# jmb575.net
KiCad netlist of a schematic drawn in Altium Designer
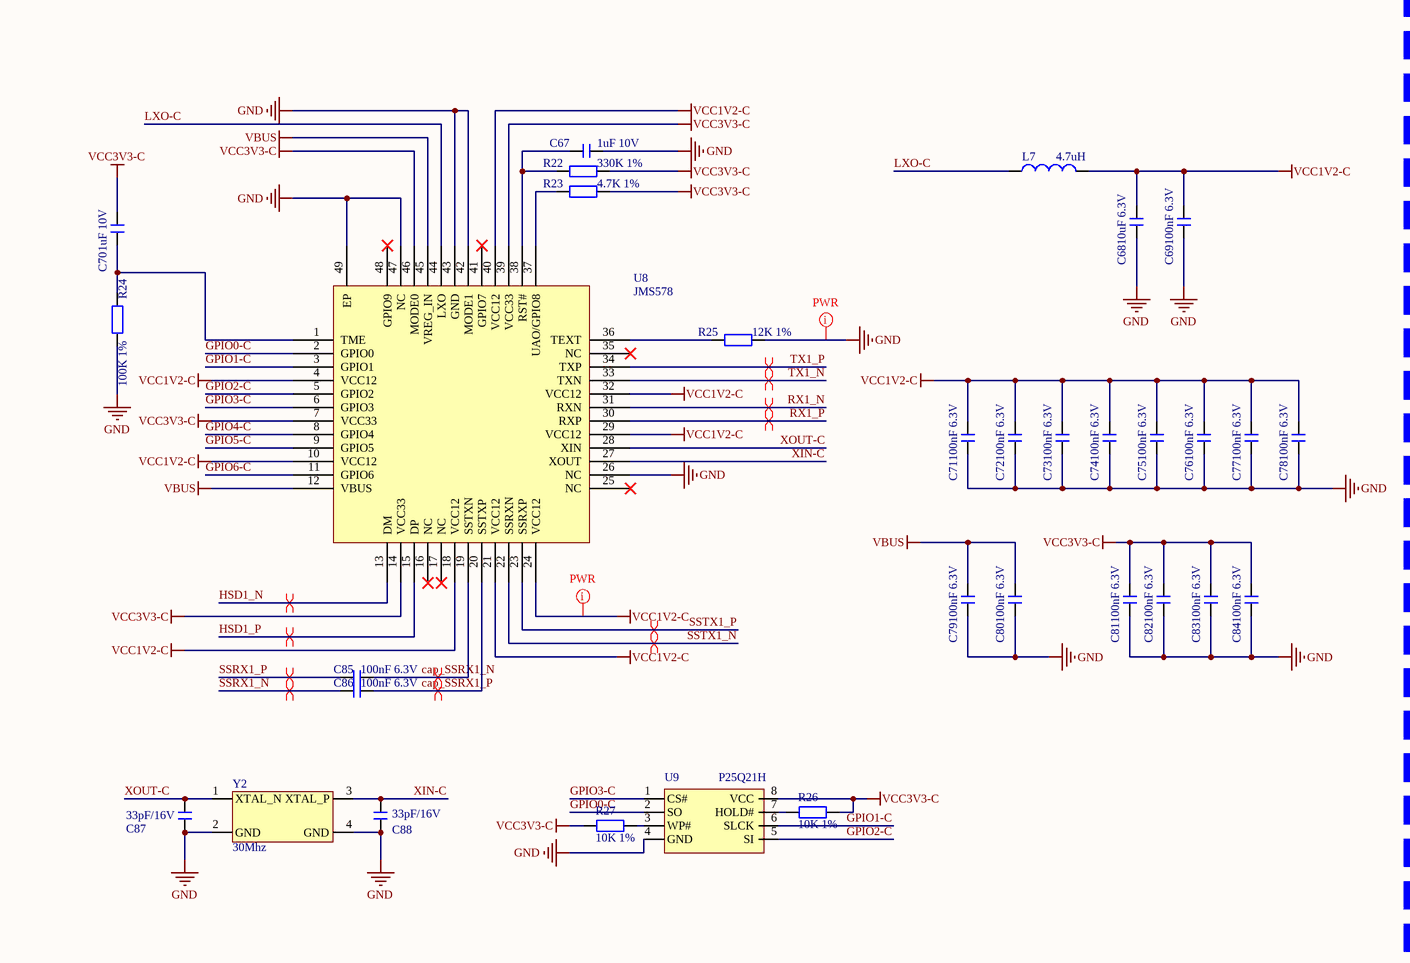
[diagram p0: jmb575.SchDoc, left]
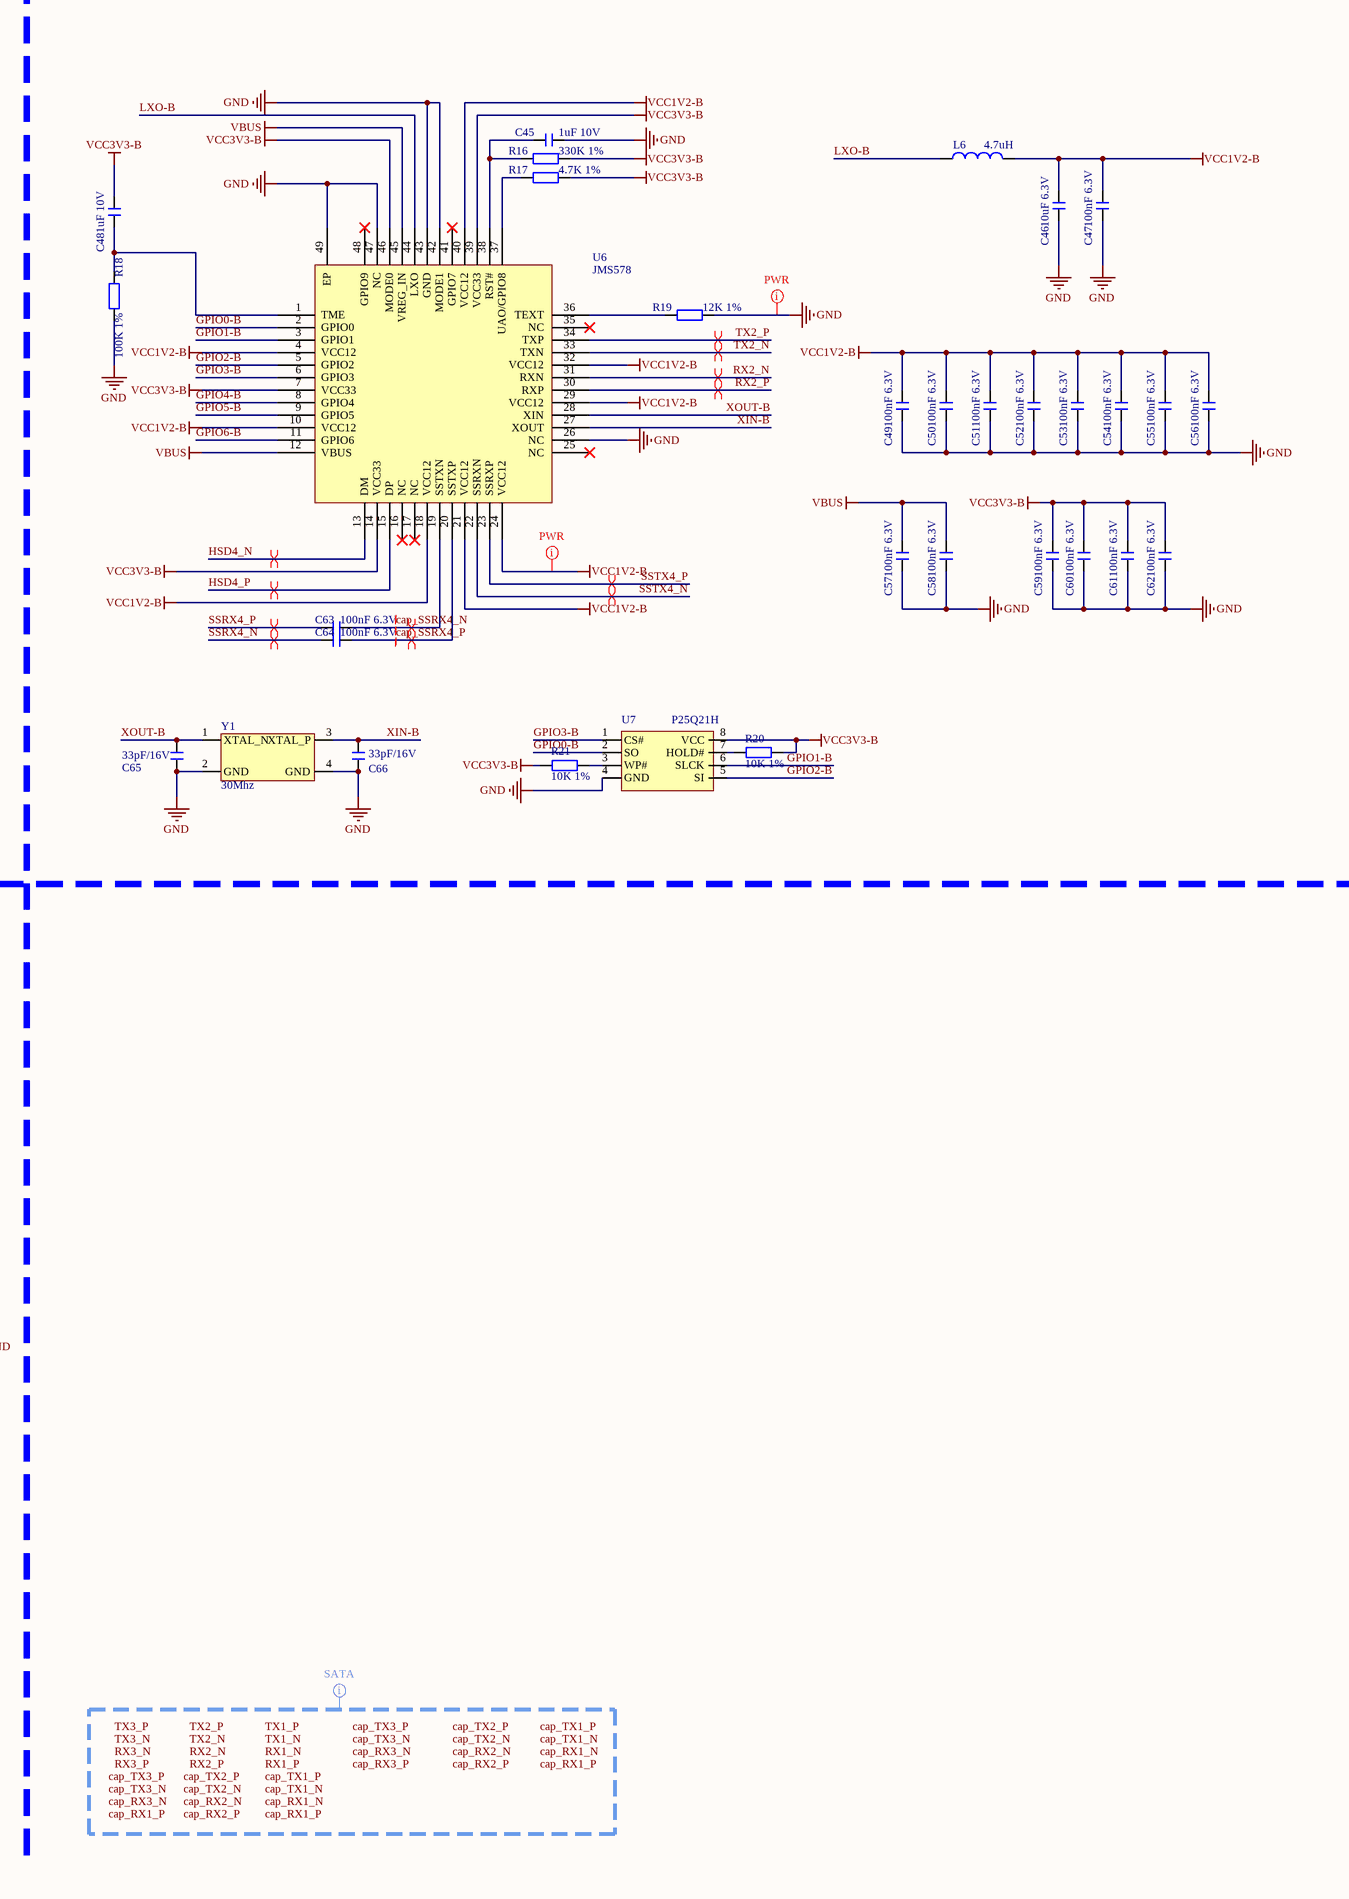
[diagram p1: jmb575.SchDoc, right]

(export (version "E")
  (design (tool "Eeschema 10.0.6"))
  (components
    (comp (ref "C45")
      (value "1uF 10V")
      (footprint "C0402_L")
      (description "无极性贴片电容")
      (fields (field (name "版权归属") "源创客"))
      (libsource (lib "Capacitor") (part "C"))
    )
    (comp (ref "C46")
      (value "10uF 6.3V")
      (footprint "C0603_L")
      (description "无极性贴片电容")
      (fields (field (name "版权归属") "源创客"))
      (libsource (lib "Capacitor") (part "C"))
    )
    (comp (ref "C47")
      (value "100nF 6.3V")
      (footprint "C0402_L")
      (description "无极性贴片电容")
      (fields (field (name "版权归属") "源创客"))
      (libsource (lib "Capacitor") (part "C"))
    )
    (comp (ref "C48")
      (value "1uF 10V")
      (footprint "C0402_L")
      (description "无极性贴片电容")
      (fields (field (name "版权归属") "源创客"))
      (libsource (lib "Capacitor") (part "C"))
    )
    (comp (ref "C49")
      (value "100nF 6.3V")
      (footprint "C0402_L")
      (description "无极性贴片电容")
      (fields (field (name "版权归属") "源创客"))
      (libsource (lib "Capacitor") (part "C"))
    )
    (comp (ref "C50")
      (value "100nF 6.3V")
      (footprint "C0402_L")
      (description "无极性贴片电容")
      (fields (field (name "版权归属") "源创客"))
      (libsource (lib "Capacitor") (part "C"))
    )
    (comp (ref "C51")
      (value "100nF 6.3V")
      (footprint "C0402_L")
      (description "无极性贴片电容")
      (fields (field (name "版权归属") "源创客"))
      (libsource (lib "Capacitor") (part "C"))
    )
    (comp (ref "C52")
      (value "100nF 6.3V")
      (footprint "C0402_L")
      (description "无极性贴片电容")
      (fields (field (name "版权归属") "源创客"))
      (libsource (lib "Capacitor") (part "C"))
    )
    (comp (ref "C53")
      (value "100nF 6.3V")
      (footprint "C0402_L")
      (description "无极性贴片电容")
      (fields (field (name "版权归属") "源创客"))
      (libsource (lib "Capacitor") (part "C"))
    )
    (comp (ref "C54")
      (value "100nF 6.3V")
      (footprint "C0402_L")
      (description "无极性贴片电容")
      (fields (field (name "版权归属") "源创客"))
      (libsource (lib "Capacitor") (part "C"))
    )
    (comp (ref "C55")
      (value "100nF 6.3V")
      (footprint "C0402_L")
      (description "无极性贴片电容")
      (fields (field (name "版权归属") "源创客"))
      (libsource (lib "Capacitor") (part "C"))
    )
    (comp (ref "C56")
      (value "100nF 6.3V")
      (footprint "C0402_L")
      (description "无极性贴片电容")
      (fields (field (name "版权归属") "源创客"))
      (libsource (lib "Capacitor") (part "C"))
    )
    (comp (ref "C57")
      (value "100nF 6.3V")
      (footprint "C0402_L")
      (description "无极性贴片电容")
      (fields (field (name "版权归属") "源创客"))
      (libsource (lib "Capacitor") (part "C"))
    )
    (comp (ref "C58")
      (value "100nF 6.3V")
      (footprint "C0402_L")
      (description "无极性贴片电容")
      (fields (field (name "版权归属") "源创客"))
      (libsource (lib "Capacitor") (part "C"))
    )
    (comp (ref "C59")
      (value "100nF 6.3V")
      (footprint "C0402_L")
      (description "无极性贴片电容")
      (fields (field (name "版权归属") "源创客"))
      (libsource (lib "Capacitor") (part "C"))
    )
    (comp (ref "C60")
      (value "100nF 6.3V")
      (footprint "C0402_L")
      (description "无极性贴片电容")
      (fields (field (name "版权归属") "源创客"))
      (libsource (lib "Capacitor") (part "C"))
    )
    (comp (ref "C61")
      (value "100nF 6.3V")
      (footprint "C0402_L")
      (description "无极性贴片电容")
      (fields (field (name "版权归属") "源创客"))
      (libsource (lib "Capacitor") (part "C"))
    )
    (comp (ref "C62")
      (value "100nF 6.3V")
      (footprint "C0402_L")
      (description "无极性贴片电容")
      (fields (field (name "版权归属") "源创客"))
      (libsource (lib "Capacitor") (part "C"))
    )
    (comp (ref "C63")
      (value "100nF 6.3V")
      (footprint "C0402_L")
      (description "无极性贴片电容")
      (fields (field (name "版权归属") "源创客"))
      (libsource (lib "Capacitor") (part "C"))
    )
    (comp (ref "C64")
      (value "100nF 6.3V")
      (footprint "C0402_L")
      (description "无极性贴片电容")
      (fields (field (name "版权归属") "源创客"))
      (libsource (lib "Capacitor") (part "C"))
    )
    (comp (ref "C65")
      (value "33pF/16V")
      (footprint "C0402_L")
      (description "无极性贴片电容")
      (fields (field (name "版权归属") "源创客"))
      (libsource (lib "Capacitor") (part "C"))
    )
    (comp (ref "C66")
      (value "33pF/16V")
      (footprint "C0402_L")
      (description "无极性贴片电容")
      (fields (field (name "版权归属") "源创客"))
      (libsource (lib "Capacitor") (part "C"))
    )
    (comp (ref "C67")
      (value "1uF 10V")
      (footprint "C0402_L")
      (description "无极性贴片电容")
      (fields (field (name "版权归属") "源创客"))
      (libsource (lib "Capacitor") (part "C"))
    )
    (comp (ref "C68")
      (value "10uF 6.3V")
      (footprint "C0603_L")
      (description "无极性贴片电容")
      (fields (field (name "版权归属") "源创客"))
      (libsource (lib "Capacitor") (part "C"))
    )
    (comp (ref "C69")
      (value "100nF 6.3V")
      (footprint "C0402_L")
      (description "无极性贴片电容")
      (fields (field (name "版权归属") "源创客"))
      (libsource (lib "Capacitor") (part "C"))
    )
    (comp (ref "C70")
      (value "1uF 10V")
      (footprint "C0402_L")
      (description "无极性贴片电容")
      (fields (field (name "版权归属") "源创客"))
      (libsource (lib "Capacitor") (part "C"))
    )
    (comp (ref "C71")
      (value "100nF 6.3V")
      (footprint "C0402_L")
      (description "无极性贴片电容")
      (fields (field (name "版权归属") "源创客"))
      (libsource (lib "Capacitor") (part "C"))
    )
    (comp (ref "C72")
      (value "100nF 6.3V")
      (footprint "C0402_L")
      (description "无极性贴片电容")
      (fields (field (name "版权归属") "源创客"))
      (libsource (lib "Capacitor") (part "C"))
    )
    (comp (ref "C73")
      (value "100nF 6.3V")
      (footprint "C0402_L")
      (description "无极性贴片电容")
      (fields (field (name "版权归属") "源创客"))
      (libsource (lib "Capacitor") (part "C"))
    )
    (comp (ref "C74")
      (value "100nF 6.3V")
      (footprint "C0402_L")
      (description "无极性贴片电容")
      (fields (field (name "版权归属") "源创客"))
      (libsource (lib "Capacitor") (part "C"))
    )
    (comp (ref "C75")
      (value "100nF 6.3V")
      (footprint "C0402_L")
      (description "无极性贴片电容")
      (fields (field (name "版权归属") "源创客"))
      (libsource (lib "Capacitor") (part "C"))
    )
    (comp (ref "C76")
      (value "100nF 6.3V")
      (footprint "C0402_L")
      (description "无极性贴片电容")
      (fields (field (name "版权归属") "源创客"))
      (libsource (lib "Capacitor") (part "C"))
    )
    (comp (ref "C77")
      (value "100nF 6.3V")
      (footprint "C0402_L")
      (description "无极性贴片电容")
      (fields (field (name "版权归属") "源创客"))
      (libsource (lib "Capacitor") (part "C"))
    )
    (comp (ref "C78")
      (value "100nF 6.3V")
      (footprint "C0402_L")
      (description "无极性贴片电容")
      (fields (field (name "版权归属") "源创客"))
      (libsource (lib "Capacitor") (part "C"))
    )
    (comp (ref "C79")
      (value "100nF 6.3V")
      (footprint "C0402_L")
      (description "无极性贴片电容")
      (fields (field (name "版权归属") "源创客"))
      (libsource (lib "Capacitor") (part "C"))
    )
    (comp (ref "C80")
      (value "100nF 6.3V")
      (footprint "C0402_L")
      (description "无极性贴片电容")
      (fields (field (name "版权归属") "源创客"))
      (libsource (lib "Capacitor") (part "C"))
    )
    (comp (ref "C81")
      (value "100nF 6.3V")
      (footprint "C0402_L")
      (description "无极性贴片电容")
      (fields (field (name "版权归属") "源创客"))
      (libsource (lib "Capacitor") (part "C"))
    )
    (comp (ref "C82")
      (value "100nF 6.3V")
      (footprint "C0402_L")
      (description "无极性贴片电容")
      (fields (field (name "版权归属") "源创客"))
      (libsource (lib "Capacitor") (part "C"))
    )
    (comp (ref "C83")
      (value "100nF 6.3V")
      (footprint "C0402_L")
      (description "无极性贴片电容")
      (fields (field (name "版权归属") "源创客"))
      (libsource (lib "Capacitor") (part "C"))
    )
    (comp (ref "C84")
      (value "100nF 6.3V")
      (footprint "C0402_L")
      (description "无极性贴片电容")
      (fields (field (name "版权归属") "源创客"))
      (libsource (lib "Capacitor") (part "C"))
    )
    (comp (ref "C85")
      (value "100nF 6.3V")
      (footprint "C0402_L")
      (description "无极性贴片电容")
      (fields (field (name "版权归属") "源创客"))
      (libsource (lib "Capacitor") (part "C"))
    )
    (comp (ref "C86")
      (value "100nF 6.3V")
      (footprint "C0402_L")
      (description "无极性贴片电容")
      (fields (field (name "版权归属") "源创客"))
      (libsource (lib "Capacitor") (part "C"))
    )
    (comp (ref "C87")
      (value "33pF/16V")
      (footprint "C0402_L")
      (description "无极性贴片电容")
      (fields (field (name "版权归属") "源创客"))
      (libsource (lib "Capacitor") (part "C"))
    )
    (comp (ref "C88")
      (value "33pF/16V")
      (footprint "C0402_L")
      (description "无极性贴片电容")
      (fields (field (name "版权归属") "源创客"))
      (libsource (lib "Capacitor") (part "C"))
    )
    (comp (ref "L6")
      (value "4.7uH")
      (footprint "SMMS0420")
      (description "小功率贴片电感")
      (fields (field (name "版权归属") "源创客"))
      (libsource (lib "Inductor") (part "L"))
    )
    (comp (ref "L7")
      (value "4.7uH")
      (footprint "SMMS0420")
      (description "小功率贴片电感")
      (fields (field (name "版权归属") "源创客"))
      (libsource (lib "Inductor") (part "L"))
    )
    (comp (ref "R16")
      (value "330K 1%")
      (footprint "R0402_L")
      (description "贴片电阻")
      (fields (field (name "版权归属") "源创客"))
      (libsource (lib "Resistor") (part "R"))
    )
    (comp (ref "R17")
      (value "4.7K 1%")
      (footprint "R0402_L")
      (description "贴片电阻")
      (fields (field (name "版权归属") "源创客"))
      (libsource (lib "Resistor") (part "R"))
    )
    (comp (ref "R18")
      (value "100K 1%")
      (footprint "R0402_L")
      (description "贴片电阻")
      (fields (field (name "版权归属") "源创客"))
      (libsource (lib "Resistor") (part "R"))
    )
    (comp (ref "R19")
      (value "12K 1%")
      (footprint "R0402_L")
      (description "贴片电阻")
      (fields (field (name "版权归属") "源创客"))
      (libsource (lib "Resistor") (part "R"))
    )
    (comp (ref "R20")
      (value "10K 1%")
      (footprint "R0402_L")
      (description "贴片电阻")
      (fields (field (name "版权归属") "源创客"))
      (libsource (lib "Resistor") (part "R"))
    )
    (comp (ref "R21")
      (value "10K 1%")
      (footprint "R0402_L")
      (description "贴片电阻")
      (fields (field (name "版权归属") "源创客"))
      (libsource (lib "Resistor") (part "R"))
    )
    (comp (ref "R22")
      (value "330K 1%")
      (footprint "R0402_L")
      (description "贴片电阻")
      (fields (field (name "版权归属") "源创客"))
      (libsource (lib "Resistor") (part "R"))
    )
    (comp (ref "R23")
      (value "4.7K 1%")
      (footprint "R0402_L")
      (description "贴片电阻")
      (fields (field (name "版权归属") "源创客"))
      (libsource (lib "Resistor") (part "R"))
    )
    (comp (ref "R24")
      (value "100K 1%")
      (footprint "R0402_L")
      (description "贴片电阻")
      (fields (field (name "版权归属") "源创客"))
      (libsource (lib "Resistor") (part "R"))
    )
    (comp (ref "R25")
      (value "12K 1%")
      (footprint "R0402_L")
      (description "贴片电阻")
      (fields (field (name "版权归属") "源创客"))
      (libsource (lib "Resistor") (part "R"))
    )
    (comp (ref "R26")
      (value "10K 1%")
      (footprint "R0402_L")
      (description "贴片电阻")
      (fields (field (name "版权归属") "源创客"))
      (libsource (lib "Resistor") (part "R"))
    )
    (comp (ref "R27")
      (value "10K 1%")
      (footprint "R0402_L")
      (description "贴片电阻")
      (fields (field (name "版权归属") "源创客"))
      (libsource (lib "Resistor") (part "R"))
    )
    (comp (ref "U6")
      (value "JMS578")
      (footprint "QFN48-L6.0-W6.0-P0.4")
      (libsource (lib "Brage") (part "JMS578"))
    )
    (comp (ref "U7") (value "P25Q21H") (footprint "SOP8_L") (libsource (lib "Flash") (part "P25D40H")))
    (comp (ref "U8")
      (value "JMS578")
      (footprint "QFN48-L6.0-W6.0-P0.4")
      (libsource (lib "Brage") (part "JMS578"))
    )
    (comp (ref "U9") (value "P25Q21H") (footprint "SOP8_L") (libsource (lib "Flash") (part "P25D40H")))
    (comp (ref "Y1") (value "30Mhz") (footprint "OSC 3225-4P") (libsource (lib "Crystal") (part "Crystal")))
    (comp (ref "Y2") (value "30Mhz") (footprint "OSC 3225-4P") (libsource (lib "Crystal") (part "Crystal")))
  )
  (nets
    (net (code "1") (name "/GPIO0-B") (class "Default")
      (node (ref "U6") (pin "2") (pinfunction "GPIO0_2") (pintype "passive"))
      (node (ref "U7") (pin "2") (pinfunction "SO_2") (pintype "passive"))
    )
    (net (code "2") (name "/GPIO0-C") (class "Default")
      (node (ref "U8") (pin "2") (pinfunction "GPIO0_2") (pintype "passive"))
      (node (ref "U9") (pin "2") (pinfunction "SO_2") (pintype "passive"))
    )
    (net (code "3") (name "/GPIO1-B") (class "Default")
      (node (ref "U6") (pin "3") (pinfunction "GPIO1_3") (pintype "passive"))
      (node (ref "U7") (pin "6") (pinfunction "SLCK_6") (pintype "passive"))
    )
    (net (code "4") (name "/GPIO1-C") (class "Default")
      (node (ref "U8") (pin "3") (pinfunction "GPIO1_3") (pintype "passive"))
      (node (ref "U9") (pin "6") (pinfunction "SLCK_6") (pintype "passive"))
    )
    (net (code "5") (name "/GPIO2-B") (class "Default")
      (node (ref "U6") (pin "5") (pinfunction "GPIO2_5") (pintype "passive"))
      (node (ref "U7") (pin "5") (pinfunction "SI_5") (pintype "passive"))
    )
    (net (code "6") (name "/GPIO2-C") (class "Default")
      (node (ref "U8") (pin "5") (pinfunction "GPIO2_5") (pintype "passive"))
      (node (ref "U9") (pin "5") (pinfunction "SI_5") (pintype "passive"))
    )
    (net (code "7") (name "/GPIO3-B") (class "Default")
      (node (ref "U6") (pin "6") (pinfunction "GPIO3_6") (pintype "passive"))
      (node (ref "U7") (pin "1") (pinfunction "CS#_1") (pintype "passive"))
    )
    (net (code "8") (name "/GPIO3-C") (class "Default")
      (node (ref "U8") (pin "6") (pinfunction "GPIO3_6") (pintype "passive"))
      (node (ref "U9") (pin "1") (pinfunction "CS#_1") (pintype "passive"))
    )
    (net (code "9") (name "/GPIO4-B") (class "Default")
      (node (ref "U6") (pin "8") (pinfunction "GPIO4_8") (pintype "passive"))
    )
    (net (code "10") (name "/GPIO4-C") (class "Default")
      (node (ref "U8") (pin "8") (pinfunction "GPIO4_8") (pintype "passive"))
    )
    (net (code "11") (name "/GPIO5-B") (class "Default")
      (node (ref "U6") (pin "9") (pinfunction "GPIO5_9") (pintype "passive"))
    )
    (net (code "12") (name "/GPIO5-C") (class "Default")
      (node (ref "U8") (pin "9") (pinfunction "GPIO5_9") (pintype "passive"))
    )
    (net (code "13") (name "/GPIO6-B") (class "Default")
      (node (ref "U6") (pin "11") (pinfunction "GPIO6_11") (pintype "passive"))
    )
    (net (code "14") (name "/GPIO6-C") (class "Default")
      (node (ref "U8") (pin "11") (pinfunction "GPIO6_11") (pintype "passive"))
    )
    (net (code "15") (name "/HSD1_N") (class "Default")
      (node (ref "U8") (pin "13") (pinfunction "DM_13") (pintype "passive"))
    )
    (net (code "16") (name "/HSD1_P") (class "Default")
      (node (ref "U8") (pin "15") (pinfunction "DP_15") (pintype "passive"))
    )
    (net (code "17") (name "/HSD4_N") (class "Default")
      (node (ref "U6") (pin "13") (pinfunction "DM_13") (pintype "passive"))
    )
    (net (code "18") (name "/HSD4_P") (class "Default")
      (node (ref "U6") (pin "15") (pinfunction "DP_15") (pintype "passive"))
    )
    (net (code "19") (name "/LXO-B") (class "Default")
      (node (ref "L6") (pin "1") (pinfunction "1_1") (pintype "passive"))
      (node (ref "U6") (pin "44") (pinfunction "LXO_44") (pintype "passive"))
    )
    (net (code "20") (name "/LXO-C") (class "Default")
      (node (ref "L7") (pin "1") (pinfunction "1_1") (pintype "passive"))
      (node (ref "U8") (pin "44") (pinfunction "LXO_44") (pintype "passive"))
    )
    (net (code "21") (name "/RX1_N") (class "Default")
      (node (ref "U8") (pin "31") (pinfunction "RXN_31") (pintype "passive"))
    )
    (net (code "22") (name "/RX1_P") (class "Default")
      (node (ref "U8") (pin "30") (pinfunction "RXP_30") (pintype "passive"))
    )
    (net (code "23") (name "/RX2_N") (class "Default")
      (node (ref "U6") (pin "31") (pinfunction "RXN_31") (pintype "passive"))
    )
    (net (code "24") (name "/RX2_P") (class "Default")
      (node (ref "U6") (pin "30") (pinfunction "RXP_30") (pintype "passive"))
    )
    (net (code "27") (name "/SSRX1_N") (class "Default")
      (node (ref "C86") (pin "1") (pinfunction "1_1") (pintype "passive"))
    )
    (net (code "28") (name "/SSRX1_P") (class "Default")
      (node (ref "C85") (pin "1") (pinfunction "1_1") (pintype "passive"))
    )
    (net (code "29") (name "/SSRX4_N") (class "Default")
      (node (ref "C64") (pin "1") (pinfunction "1_1") (pintype "passive"))
    )
    (net (code "30") (name "/SSRX4_P") (class "Default")
      (node (ref "C63") (pin "1") (pinfunction "1_1") (pintype "passive"))
    )
    (net (code "31") (name "/SSTX1_N") (class "Default")
      (node (ref "U8") (pin "22") (pinfunction "SSRXN_22") (pintype "passive"))
    )
    (net (code "32") (name "/SSTX1_P") (class "Default")
      (node (ref "U8") (pin "23") (pinfunction "SSRXP_23") (pintype "passive"))
    )
    (net (code "33") (name "/SSTX4_N") (class "Default")
      (node (ref "U6") (pin "22") (pinfunction "SSRXN_22") (pintype "passive"))
    )
    (net (code "34") (name "/SSTX4_P") (class "Default")
      (node (ref "U6") (pin "23") (pinfunction "SSRXP_23") (pintype "passive"))
    )
    (net (code "35") (name "/TX1_N") (class "Default")
      (node (ref "U8") (pin "33") (pinfunction "TXN_33") (pintype "passive"))
    )
    (net (code "36") (name "/TX1_P") (class "Default")
      (node (ref "U8") (pin "34") (pinfunction "TXP_34") (pintype "passive"))
    )
    (net (code "37") (name "/TX2_N") (class "Default")
      (node (ref "U6") (pin "33") (pinfunction "TXN_33") (pintype "passive"))
    )
    (net (code "38") (name "/TX2_P") (class "Default")
      (node (ref "U6") (pin "34") (pinfunction "TXP_34") (pintype "passive"))
    )
    (net (code "41") (name "/XIN-B") (class "Default")
      (node (ref "C66") (pin "1") (pinfunction "1_1") (pintype "passive"))
      (node (ref "U6") (pin "27") (pinfunction "XOUT_27") (pintype "passive"))
      (node (ref "Y1") (pin "3") (pinfunction "XTAL_P_3") (pintype "passive"))
    )
    (net (code "42") (name "/XIN-C") (class "Default")
      (node (ref "C88") (pin "1") (pinfunction "1_1") (pintype "passive"))
      (node (ref "U8") (pin "27") (pinfunction "XOUT_27") (pintype "passive"))
      (node (ref "Y2") (pin "3") (pinfunction "XTAL_P_3") (pintype "passive"))
    )
    (net (code "43") (name "/XOUT-B") (class "Default")
      (node (ref "C65") (pin "1") (pinfunction "1_1") (pintype "passive"))
      (node (ref "U6") (pin "28") (pinfunction "XIN_28") (pintype "passive"))
      (node (ref "Y1") (pin "1") (pinfunction "XTAL_N_1") (pintype "passive"))
    )
    (net (code "44") (name "/XOUT-C") (class "Default")
      (node (ref "C87") (pin "1") (pinfunction "1_1") (pintype "passive"))
      (node (ref "U8") (pin "28") (pinfunction "XIN_28") (pintype "passive"))
      (node (ref "Y2") (pin "1") (pinfunction "XTAL_N_1") (pintype "passive"))
    )
    (net (code "51") (name "/cap_SSRX1_N") (class "Default")
      (node (ref "C85") (pin "2") (pinfunction "2_2") (pintype "passive"))
      (node (ref "U8") (pin "19") (pinfunction "SSTXN_19") (pintype "passive"))
    )
    (net (code "52") (name "/cap_SSRX1_P") (class "Default")
      (node (ref "C86") (pin "2") (pinfunction "2_2") (pintype "passive"))
      (node (ref "U8") (pin "20") (pinfunction "SSTXP_20") (pintype "passive"))
    )
    (net (code "53") (name "/cap_SSRX4_N") (class "Default")
      (node (ref "C63") (pin "2") (pinfunction "2_2") (pintype "passive"))
      (node (ref "U6") (pin "19") (pinfunction "SSTXN_19") (pintype "passive"))
    )
    (net (code "54") (name "/cap_SSRX4_P") (class "Default")
      (node (ref "C64") (pin "2") (pinfunction "2_2") (pintype "passive"))
      (node (ref "U6") (pin "20") (pinfunction "SSTXP_20") (pintype "passive"))
    )
    (net (code "61") (name "GND") (class "Default")
      (node (ref "C45") (pin "1") (pinfunction "1_1") (pintype "passive"))
      (node (ref "C46") (pin "1") (pinfunction "1_1") (pintype "passive"))
      (node (ref "C47") (pin "1") (pinfunction "1_1") (pintype "passive"))
      (node (ref "C49") (pin "1") (pinfunction "1_1") (pintype "passive"))
      (node (ref "C50") (pin "1") (pinfunction "1_1") (pintype "passive"))
      (node (ref "C51") (pin "1") (pinfunction "1_1") (pintype "passive"))
      (node (ref "C52") (pin "1") (pinfunction "1_1") (pintype "passive"))
      (node (ref "C53") (pin "1") (pinfunction "1_1") (pintype "passive"))
      (node (ref "C54") (pin "1") (pinfunction "1_1") (pintype "passive"))
      (node (ref "C55") (pin "1") (pinfunction "1_1") (pintype "passive"))
      (node (ref "C56") (pin "1") (pinfunction "1_1") (pintype "passive"))
      (node (ref "C57") (pin "1") (pinfunction "1_1") (pintype "passive"))
      (node (ref "C58") (pin "1") (pinfunction "1_1") (pintype "passive"))
      (node (ref "C59") (pin "1") (pinfunction "1_1") (pintype "passive"))
      (node (ref "C60") (pin "1") (pinfunction "1_1") (pintype "passive"))
      (node (ref "C61") (pin "1") (pinfunction "1_1") (pintype "passive"))
      (node (ref "C62") (pin "1") (pinfunction "1_1") (pintype "passive"))
      (node (ref "C65") (pin "2") (pinfunction "2_2") (pintype "passive"))
      (node (ref "C66") (pin "2") (pinfunction "2_2") (pintype "passive"))
      (node (ref "C67") (pin "1") (pinfunction "1_1") (pintype "passive"))
      (node (ref "C68") (pin "1") (pinfunction "1_1") (pintype "passive"))
      (node (ref "C69") (pin "1") (pinfunction "1_1") (pintype "passive"))
      (node (ref "C71") (pin "1") (pinfunction "1_1") (pintype "passive"))
      (node (ref "C72") (pin "1") (pinfunction "1_1") (pintype "passive"))
      (node (ref "C73") (pin "1") (pinfunction "1_1") (pintype "passive"))
      (node (ref "C74") (pin "1") (pinfunction "1_1") (pintype "passive"))
      (node (ref "C75") (pin "1") (pinfunction "1_1") (pintype "passive"))
      (node (ref "C76") (pin "1") (pinfunction "1_1") (pintype "passive"))
      (node (ref "C77") (pin "1") (pinfunction "1_1") (pintype "passive"))
      (node (ref "C78") (pin "1") (pinfunction "1_1") (pintype "passive"))
      (node (ref "C79") (pin "1") (pinfunction "1_1") (pintype "passive"))
      (node (ref "C80") (pin "1") (pinfunction "1_1") (pintype "passive"))
      (node (ref "C81") (pin "1") (pinfunction "1_1") (pintype "passive"))
      (node (ref "C82") (pin "1") (pinfunction "1_1") (pintype "passive"))
      (node (ref "C83") (pin "1") (pinfunction "1_1") (pintype "passive"))
      (node (ref "C84") (pin "1") (pinfunction "1_1") (pintype "passive"))
      (node (ref "C87") (pin "2") (pinfunction "2_2") (pintype "passive"))
      (node (ref "C88") (pin "2") (pinfunction "2_2") (pintype "passive"))
      (node (ref "R18") (pin "1") (pinfunction "1_1") (pintype "passive"))
      (node (ref "R19") (pin "1") (pinfunction "1_1") (pintype "passive"))
      (node (ref "R24") (pin "1") (pinfunction "1_1") (pintype "passive"))
      (node (ref "R25") (pin "1") (pinfunction "1_1") (pintype "passive"))
      (node (ref "U6") (pin "26") (pinfunction "NC_26") (pintype "passive"))
      (node (ref "U6") (pin "42") (pinfunction "MODE1_42") (pintype "passive"))
      (node (ref "U6") (pin "43") (pinfunction "GND_43") (pintype "passive"))
      (node (ref "U6") (pin "47") (pinfunction "NC_47") (pintype "passive"))
      (node (ref "U6") (pin "49") (pinfunction "EP_49") (pintype "passive"))
      (node (ref "U7") (pin "4") (pinfunction "GND_4") (pintype "passive"))
      (node (ref "U8") (pin "26") (pinfunction "NC_26") (pintype "passive"))
      (node (ref "U8") (pin "42") (pinfunction "MODE1_42") (pintype "passive"))
      (node (ref "U8") (pin "43") (pinfunction "GND_43") (pintype "passive"))
      (node (ref "U8") (pin "47") (pinfunction "NC_47") (pintype "passive"))
      (node (ref "U8") (pin "49") (pinfunction "EP_49") (pintype "passive"))
      (node (ref "U9") (pin "4") (pinfunction "GND_4") (pintype "passive"))
      (node (ref "Y1") (pin "2") (pinfunction "GND_2") (pintype "passive"))
      (node (ref "Y1") (pin "4") (pinfunction "GND_4") (pintype "passive"))
      (node (ref "Y2") (pin "2") (pinfunction "GND_2") (pintype "passive"))
      (node (ref "Y2") (pin "4") (pinfunction "GND_4") (pintype "passive"))
    )
    (net (code "62") (name "Net-(U6-RST#)") (class "Default")
      (node (ref "C45") (pin "2") (pinfunction "2_2") (pintype "passive"))
      (node (ref "R16") (pin "2") (pinfunction "2_2") (pintype "passive"))
      (node (ref "U6") (pin "38") (pinfunction "RST#_38") (pintype "passive"))
    )
    (net (code "63") (name "Net-(U6-TEXT)") (class "Default")
      (node (ref "R19") (pin "2") (pinfunction "2_2") (pintype "passive"))
      (node (ref "U6") (pin "36") (pinfunction "TEXT_36") (pintype "passive"))
    )
    (net (code "64") (name "Net-(U6-TME)") (class "Default")
      (node (ref "C48") (pin "1") (pinfunction "1_1") (pintype "passive"))
      (node (ref "R18") (pin "2") (pinfunction "2_2") (pintype "passive"))
      (node (ref "U6") (pin "1") (pinfunction "TME_1") (pintype "passive"))
    )
    (net (code "65") (name "Net-(U6-UAO{slash}GPIO8)") (class "Default")
      (node (ref "R17") (pin "2") (pinfunction "2_2") (pintype "passive"))
      (node (ref "U6") (pin "37") (pinfunction "UAO/GPIO8_37") (pintype "passive"))
    )
    (net (code "66") (name "Net-(U7-HOLD#)") (class "Default")
      (node (ref "R20") (pin "2") (pinfunction "2_2") (pintype "passive"))
      (node (ref "U7") (pin "7") (pinfunction "HOLD#_7") (pintype "passive"))
    )
    (net (code "67") (name "Net-(U7-WP#)") (class "Default")
      (node (ref "R21") (pin "2") (pinfunction "2_2") (pintype "passive"))
      (node (ref "U7") (pin "3") (pinfunction "WP#_3") (pintype "passive"))
    )
    (net (code "68") (name "Net-(U8-RST#)") (class "Default")
      (node (ref "C67") (pin "2") (pinfunction "2_2") (pintype "passive"))
      (node (ref "R22") (pin "2") (pinfunction "2_2") (pintype "passive"))
      (node (ref "U8") (pin "38") (pinfunction "RST#_38") (pintype "passive"))
    )
    (net (code "69") (name "Net-(U8-TEXT)") (class "Default")
      (node (ref "R25") (pin "2") (pinfunction "2_2") (pintype "passive"))
      (node (ref "U8") (pin "36") (pinfunction "TEXT_36") (pintype "passive"))
    )
    (net (code "70") (name "Net-(U8-TME)") (class "Default")
      (node (ref "C70") (pin "1") (pinfunction "1_1") (pintype "passive"))
      (node (ref "R24") (pin "2") (pinfunction "2_2") (pintype "passive"))
      (node (ref "U8") (pin "1") (pinfunction "TME_1") (pintype "passive"))
    )
    (net (code "71") (name "Net-(U8-UAO{slash}GPIO8)") (class "Default")
      (node (ref "R23") (pin "2") (pinfunction "2_2") (pintype "passive"))
      (node (ref "U8") (pin "37") (pinfunction "UAO/GPIO8_37") (pintype "passive"))
    )
    (net (code "72") (name "Net-(U9-HOLD#)") (class "Default")
      (node (ref "R26") (pin "2") (pinfunction "2_2") (pintype "passive"))
      (node (ref "U9") (pin "7") (pinfunction "HOLD#_7") (pintype "passive"))
    )
    (net (code "73") (name "Net-(U9-WP#)") (class "Default")
      (node (ref "R27") (pin "1") (pinfunction "1_1") (pintype "passive"))
      (node (ref "U9") (pin "3") (pinfunction "WP#_3") (pintype "passive"))
    )
    (net (code "74") (name "VBUS") (class "Default")
      (node (ref "C57") (pin "2") (pinfunction "2_2") (pintype "passive"))
      (node (ref "C58") (pin "2") (pinfunction "2_2") (pintype "passive"))
      (node (ref "C79") (pin "2") (pinfunction "2_2") (pintype "passive"))
      (node (ref "C80") (pin "2") (pinfunction "2_2") (pintype "passive"))
      (node (ref "U6") (pin "12") (pinfunction "VBUS_12") (pintype "passive"))
      (node (ref "U6") (pin "45") (pinfunction "VREG_IN_45") (pintype "passive"))
      (node (ref "U8") (pin "12") (pinfunction "VBUS_12") (pintype "passive"))
      (node (ref "U8") (pin "45") (pinfunction "VREG_IN_45") (pintype "passive"))
    )
    (net (code "75") (name "VCC1V2-B") (class "Default")
      (node (ref "C46") (pin "2") (pinfunction "2_2") (pintype "passive"))
      (node (ref "C47") (pin "2") (pinfunction "2_2") (pintype "passive"))
      (node (ref "C49") (pin "2") (pinfunction "2_2") (pintype "passive"))
      (node (ref "C50") (pin "2") (pinfunction "2_2") (pintype "passive"))
      (node (ref "C51") (pin "2") (pinfunction "2_2") (pintype "passive"))
      (node (ref "C52") (pin "2") (pinfunction "2_2") (pintype "passive"))
      (node (ref "C53") (pin "2") (pinfunction "2_2") (pintype "passive"))
      (node (ref "C54") (pin "2") (pinfunction "2_2") (pintype "passive"))
      (node (ref "C55") (pin "2") (pinfunction "2_2") (pintype "passive"))
      (node (ref "C56") (pin "2") (pinfunction "2_2") (pintype "passive"))
      (node (ref "L6") (pin "2") (pinfunction "2_2") (pintype "passive"))
      (node (ref "U6") (pin "10") (pinfunction "VCC12_10") (pintype "passive"))
      (node (ref "U6") (pin "18") (pinfunction "VCC12_18") (pintype "passive"))
      (node (ref "U6") (pin "21") (pinfunction "VCC12_21") (pintype "passive"))
      (node (ref "U6") (pin "24") (pinfunction "VCC12_24") (pintype "passive"))
      (node (ref "U6") (pin "29") (pinfunction "VCC12_29") (pintype "passive"))
      (node (ref "U6") (pin "32") (pinfunction "VCC12_32") (pintype "passive"))
      (node (ref "U6") (pin "4") (pinfunction "VCC12_4") (pintype "passive"))
      (node (ref "U6") (pin "40") (pinfunction "VCC12_40") (pintype "passive"))
    )
    (net (code "76") (name "VCC1V2-C") (class "Default")
      (node (ref "C68") (pin "2") (pinfunction "2_2") (pintype "passive"))
      (node (ref "C69") (pin "2") (pinfunction "2_2") (pintype "passive"))
      (node (ref "C71") (pin "2") (pinfunction "2_2") (pintype "passive"))
      (node (ref "C72") (pin "2") (pinfunction "2_2") (pintype "passive"))
      (node (ref "C73") (pin "2") (pinfunction "2_2") (pintype "passive"))
      (node (ref "C74") (pin "2") (pinfunction "2_2") (pintype "passive"))
      (node (ref "C75") (pin "2") (pinfunction "2_2") (pintype "passive"))
      (node (ref "C76") (pin "2") (pinfunction "2_2") (pintype "passive"))
      (node (ref "C77") (pin "2") (pinfunction "2_2") (pintype "passive"))
      (node (ref "C78") (pin "2") (pinfunction "2_2") (pintype "passive"))
      (node (ref "L7") (pin "2") (pinfunction "2_2") (pintype "passive"))
      (node (ref "U8") (pin "10") (pinfunction "VCC12_10") (pintype "passive"))
      (node (ref "U8") (pin "18") (pinfunction "VCC12_18") (pintype "passive"))
      (node (ref "U8") (pin "21") (pinfunction "VCC12_21") (pintype "passive"))
      (node (ref "U8") (pin "24") (pinfunction "VCC12_24") (pintype "passive"))
      (node (ref "U8") (pin "29") (pinfunction "VCC12_29") (pintype "passive"))
      (node (ref "U8") (pin "32") (pinfunction "VCC12_32") (pintype "passive"))
      (node (ref "U8") (pin "4") (pinfunction "VCC12_4") (pintype "passive"))
      (node (ref "U8") (pin "40") (pinfunction "VCC12_40") (pintype "passive"))
    )
    (net (code "77") (name "VCC3V3-B") (class "Default")
      (node (ref "C48") (pin "2") (pinfunction "2_2") (pintype "passive"))
      (node (ref "C59") (pin "2") (pinfunction "2_2") (pintype "passive"))
      (node (ref "C60") (pin "2") (pinfunction "2_2") (pintype "passive"))
      (node (ref "C61") (pin "2") (pinfunction "2_2") (pintype "passive"))
      (node (ref "C62") (pin "2") (pinfunction "2_2") (pintype "passive"))
      (node (ref "R16") (pin "1") (pinfunction "1_1") (pintype "passive"))
      (node (ref "R17") (pin "1") (pinfunction "1_1") (pintype "passive"))
      (node (ref "R20") (pin "1") (pinfunction "1_1") (pintype "passive"))
      (node (ref "R21") (pin "1") (pinfunction "1_1") (pintype "passive"))
      (node (ref "U6") (pin "14") (pinfunction "VCC33_14") (pintype "passive"))
      (node (ref "U6") (pin "39") (pinfunction "VCC33_39") (pintype "passive"))
      (node (ref "U6") (pin "46") (pinfunction "MODE0_46") (pintype "passive"))
      (node (ref "U6") (pin "7") (pinfunction "VCC33_7") (pintype "passive"))
      (node (ref "U7") (pin "8") (pinfunction "VCC_8") (pintype "passive"))
    )
    (net (code "78") (name "VCC3V3-C") (class "Default")
      (node (ref "C70") (pin "2") (pinfunction "2_2") (pintype "passive"))
      (node (ref "C81") (pin "2") (pinfunction "2_2") (pintype "passive"))
      (node (ref "C82") (pin "2") (pinfunction "2_2") (pintype "passive"))
      (node (ref "C83") (pin "2") (pinfunction "2_2") (pintype "passive"))
      (node (ref "C84") (pin "2") (pinfunction "2_2") (pintype "passive"))
      (node (ref "R22") (pin "1") (pinfunction "1_1") (pintype "passive"))
      (node (ref "R23") (pin "1") (pinfunction "1_1") (pintype "passive"))
      (node (ref "R26") (pin "1") (pinfunction "1_1") (pintype "passive"))
      (node (ref "R27") (pin "2") (pinfunction "2_2") (pintype "passive"))
      (node (ref "U8") (pin "14") (pinfunction "VCC33_14") (pintype "passive"))
      (node (ref "U8") (pin "39") (pinfunction "VCC33_39") (pintype "passive"))
      (node (ref "U8") (pin "46") (pinfunction "MODE0_46") (pintype "passive"))
      (node (ref "U8") (pin "7") (pinfunction "VCC33_7") (pintype "passive"))
      (node (ref "U9") (pin "8") (pinfunction "VCC_8") (pintype "passive"))
    )
    (net (code "79") (name "unconnected-(U6-GPIO7-Pad41)") (class "Default")
      (node (ref "U6") (pin "41") (pinfunction "GPIO7_41") (pintype "passive+no_connect"))
    )
    (net (code "80") (name "unconnected-(U6-GPIO9-Pad48)") (class "Default")
      (node (ref "U6") (pin "48") (pinfunction "GPIO9_48") (pintype "passive+no_connect"))
    )
    (net (code "81") (name "unconnected-(U6-NC-Pad16)") (class "Default")
      (node (ref "U6") (pin "16") (pinfunction "NC_16") (pintype "passive+no_connect"))
    )
    (net (code "82") (name "unconnected-(U6-NC-Pad17)") (class "Default")
      (node (ref "U6") (pin "17") (pinfunction "NC_17") (pintype "passive+no_connect"))
    )
    (net (code "83") (name "unconnected-(U6-NC-Pad25)") (class "Default")
      (node (ref "U6") (pin "25") (pinfunction "NC_25") (pintype "passive+no_connect"))
    )
    (net (code "84") (name "unconnected-(U6-NC-Pad35)") (class "Default")
      (node (ref "U6") (pin "35") (pinfunction "NC_35") (pintype "passive+no_connect"))
    )
    (net (code "85") (name "unconnected-(U8-GPIO7-Pad41)") (class "Default")
      (node (ref "U8") (pin "41") (pinfunction "GPIO7_41") (pintype "passive+no_connect"))
    )
    (net (code "86") (name "unconnected-(U8-GPIO9-Pad48)") (class "Default")
      (node (ref "U8") (pin "48") (pinfunction "GPIO9_48") (pintype "passive+no_connect"))
    )
    (net (code "87") (name "unconnected-(U8-NC-Pad16)") (class "Default")
      (node (ref "U8") (pin "16") (pinfunction "NC_16") (pintype "passive+no_connect"))
    )
    (net (code "88") (name "unconnected-(U8-NC-Pad17)") (class "Default")
      (node (ref "U8") (pin "17") (pinfunction "NC_17") (pintype "passive+no_connect"))
    )
    (net (code "89") (name "unconnected-(U8-NC-Pad25)") (class "Default")
      (node (ref "U8") (pin "25") (pinfunction "NC_25") (pintype "passive+no_connect"))
    )
    (net (code "90") (name "unconnected-(U8-NC-Pad35)") (class "Default")
      (node (ref "U8") (pin "35") (pinfunction "NC_35") (pintype "passive+no_connect"))
    )
  )
)
